# ethernet_poe.net
KiCad netlist of a schematic drawn in EAGLE
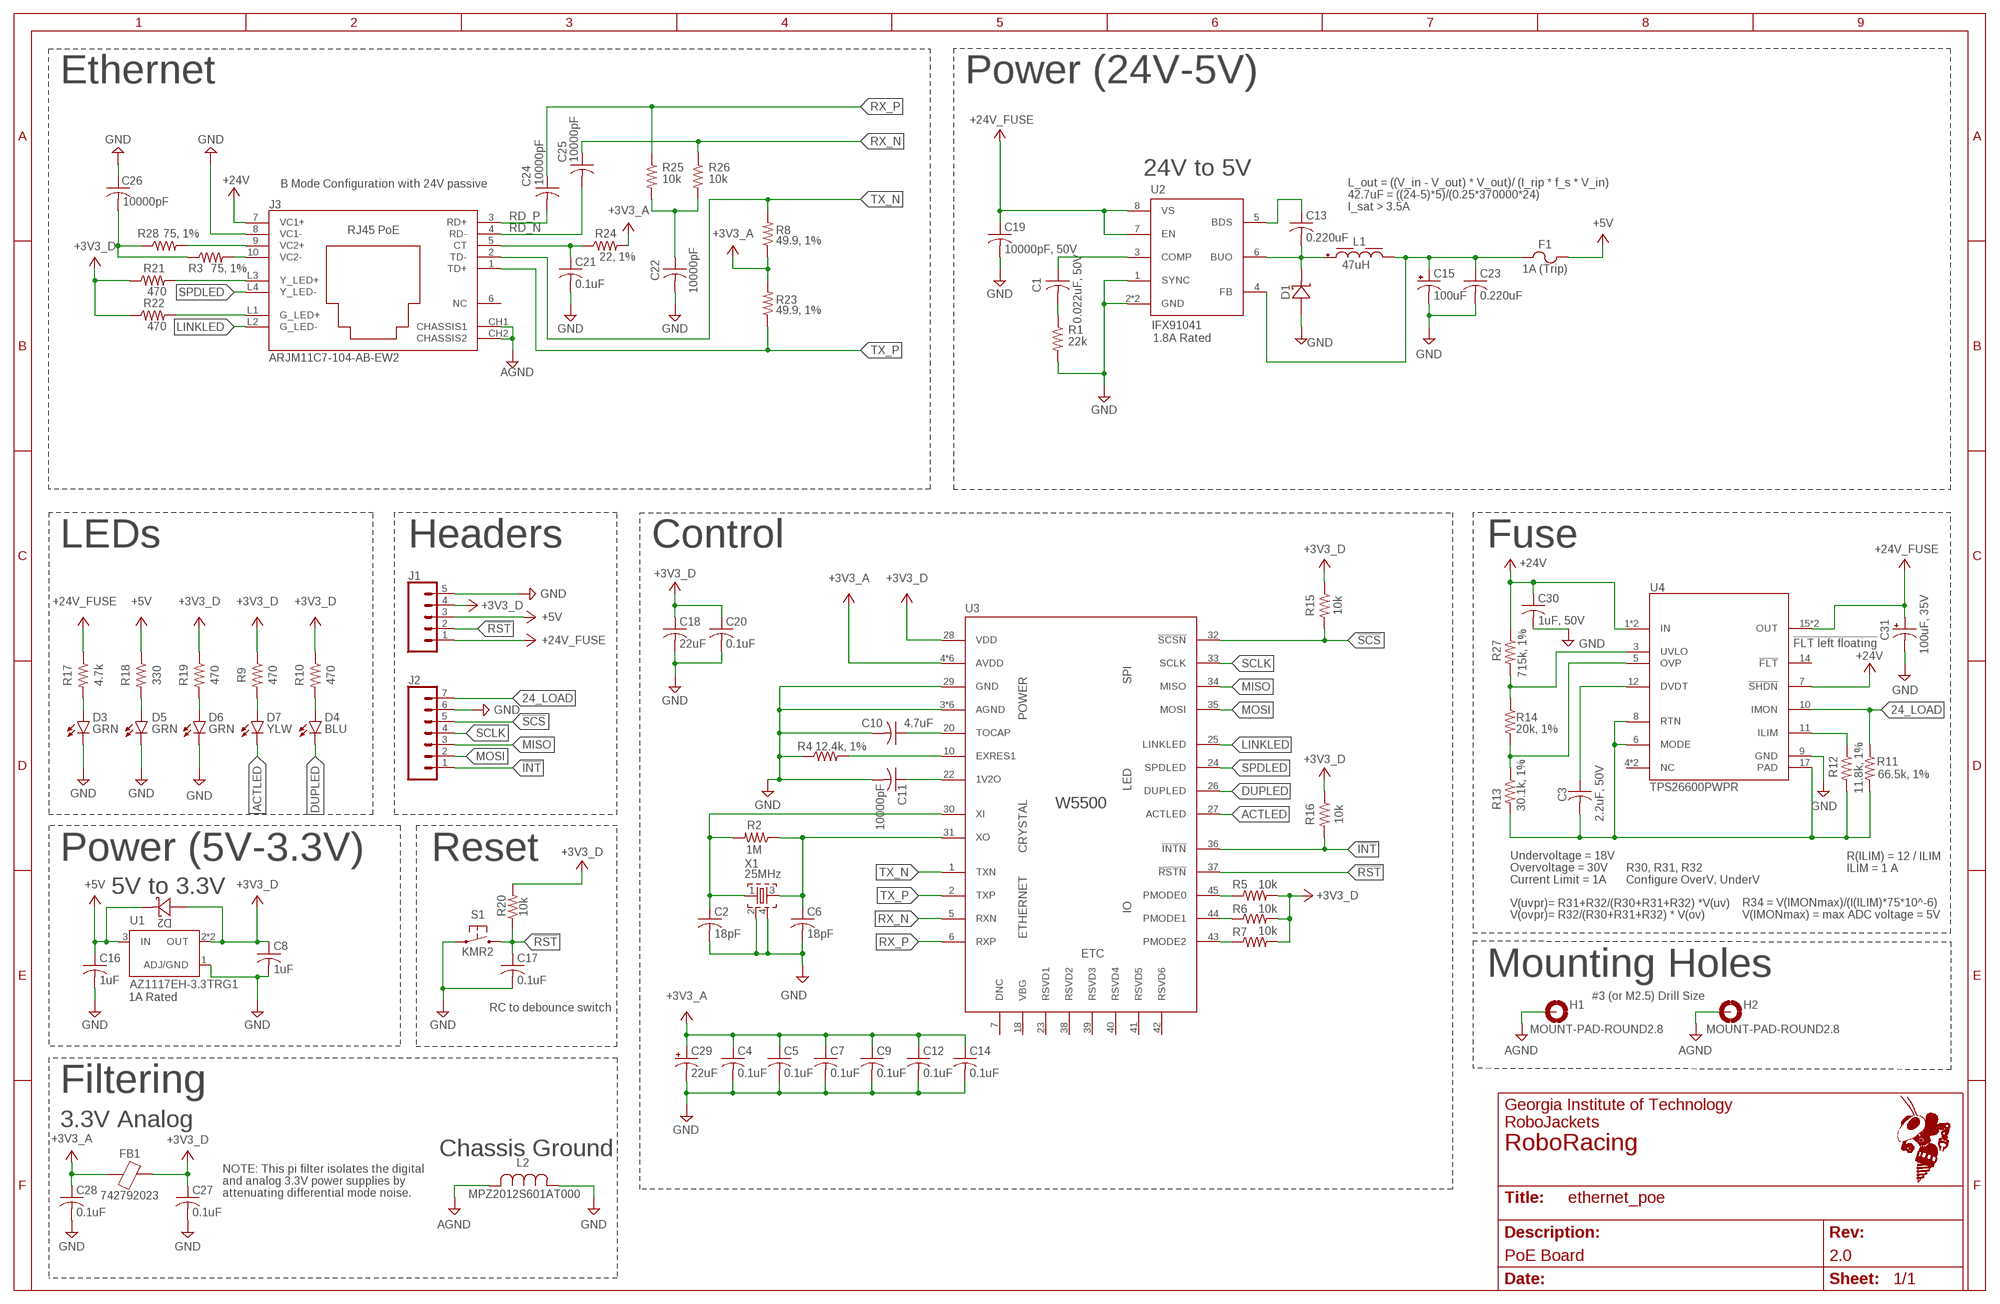
[diagram p0: schematic, sheet 1]

(export (version "E")
  (design (tool "Eeschema 10.0.6"))
  (components
    (comp (ref "C1")
      (value "0.022uF, 50V")
      (footprint "eagle-import:C0603")
      (libsource (lib "eagle-import") (part "rcl_334_C-USC0603"))
    )
    (comp (ref "C2")
      (value "18pF")
      (footprint "eagle-import:C0603")
      (libsource (lib "eagle-import") (part "rcl_334_C-USC0603"))
    )
    (comp (ref "C3")
      (value "2.2uF, 50V")
      (footprint "eagle-import:C0603")
      (libsource (lib "eagle-import") (part "rcl_334_C-USC0603"))
    )
    (comp (ref "C4")
      (value "0.1uF")
      (footprint "eagle-import:C0402")
      (libsource (lib "eagle-import") (part "C-USC0402"))
    )
    (comp (ref "C5")
      (value "0.1uF")
      (footprint "eagle-import:C0402")
      (libsource (lib "eagle-import") (part "C-USC0402"))
    )
    (comp (ref "C6")
      (value "18pF")
      (footprint "eagle-import:C0603")
      (libsource (lib "eagle-import") (part "rcl_334_C-USC0603"))
    )
    (comp (ref "C7")
      (value "0.1uF")
      (footprint "eagle-import:C0402")
      (libsource (lib "eagle-import") (part "C-USC0402"))
    )
    (comp (ref "C8")
      (value "1uF")
      (footprint "eagle-import:C0603")
      (libsource (lib "eagle-import") (part "rcl_334_C-USC0603"))
    )
    (comp (ref "C9")
      (value "0.1uF")
      (footprint "eagle-import:C0402")
      (libsource (lib "eagle-import") (part "C-USC0402"))
    )
    (comp (ref "C10")
      (value "4.7uF")
      (footprint "eagle-import:C0603")
      (libsource (lib "eagle-import") (part "rcl_334_C-USC0603"))
    )
    (comp (ref "C11")
      (value "10000pF")
      (footprint "eagle-import:C0402")
      (libsource (lib "eagle-import") (part "C-USC0402"))
    )
    (comp (ref "C12")
      (value "0.1uF")
      (footprint "eagle-import:C0402")
      (libsource (lib "eagle-import") (part "C-USC0402"))
    )
    (comp (ref "C13")
      (value "0.220uF")
      (footprint "eagle-import:C0603")
      (libsource (lib "eagle-import") (part "rcl_334_C-USC0603"))
    )
    (comp (ref "C14")
      (value "0.1uF")
      (footprint "eagle-import:C0402")
      (libsource (lib "eagle-import") (part "C-USC0402"))
    )
    (comp (ref "C15")
      (value "100uF")
      (footprint "eagle-import:E2-5")
      (libsource (lib "eagle-import") (part "CPOL-USE2-5"))
    )
    (comp (ref "C16")
      (value "1uF")
      (footprint "eagle-import:C0603")
      (libsource (lib "eagle-import") (part "rcl_334_C-USC0603"))
    )
    (comp (ref "C17")
      (value "0.1uF")
      (footprint "eagle-import:C0402")
      (libsource (lib "eagle-import") (part "C-USC0402"))
    )
    (comp (ref "C18")
      (value "22uF")
      (footprint "eagle-import:C0603")
      (libsource (lib "eagle-import") (part "rcl_334_C-USC0603"))
    )
    (comp (ref "C19")
      (value "10000pF, 50V")
      (footprint "eagle-import:C0603")
      (libsource (lib "eagle-import") (part "rcl_334_C-USC0603"))
    )
    (comp (ref "C20")
      (value "0.1uF")
      (footprint "eagle-import:C0402")
      (libsource (lib "eagle-import") (part "C-USC0402"))
    )
    (comp (ref "C21")
      (value "0.1uF")
      (footprint "eagle-import:C0402")
      (libsource (lib "eagle-import") (part "C-USC0402"))
    )
    (comp (ref "C22")
      (value "10000pF")
      (footprint "eagle-import:C0603")
      (libsource (lib "eagle-import") (part "rcl_334_C-USC0603"))
    )
    (comp (ref "C23")
      (value "0.220uF")
      (footprint "eagle-import:C0603")
      (libsource (lib "eagle-import") (part "rcl_334_C-USC0603"))
    )
    (comp (ref "C24")
      (value "10000pF")
      (footprint "eagle-import:C0402")
      (libsource (lib "eagle-import") (part "C-USC0402"))
    )
    (comp (ref "C25")
      (value "10000pF")
      (footprint "eagle-import:C0402")
      (libsource (lib "eagle-import") (part "C-USC0402"))
    )
    (comp (ref "C26")
      (value "10000pF")
      (footprint "eagle-import:C0603")
      (libsource (lib "eagle-import") (part "rcl_334_C-USC0603"))
    )
    (comp (ref "C27")
      (value "0.1uF")
      (footprint "eagle-import:C0603")
      (libsource (lib "eagle-import") (part "C-USC0603"))
    )
    (comp (ref "C28")
      (value "0.1uF")
      (footprint "eagle-import:C0603")
      (libsource (lib "eagle-import") (part "C-USC0603"))
    )
    (comp (ref "C29")
      (value "22uF")
      (footprint "eagle-import:PANASONIC_C")
      (libsource (lib "eagle-import") (part "22UF-POLAR-PANASONIC_C-35V-20%"))
    )
    (comp (ref "C30")
      (value "1uF, 50V")
      (footprint "eagle-import:C0603")
      (libsource (lib "eagle-import") (part "rcl_334_C-USC0603"))
    )
    (comp (ref "C31")
      (value "100uF, 35V")
      (footprint "eagle-import:E2,5-7")
      (libsource (lib "eagle-import") (part "CPOL-USE2.5-7"))
    )
    (comp (ref "D1")
      (value "NTS260ESFT3G")
      (footprint "eagle-import:SOD123FL_DIO")
      (libsource (lib "eagle-import") (part "NTS260ESFT3G"))
    )
    (comp (ref "D2")
      (value "NTS260ESFT3G")
      (footprint "eagle-import:SOD123FL_DIO")
      (libsource (lib "eagle-import") (part "NTS260ESFT3G"))
    )
    (comp (ref "D3")
      (value "GRN")
      (footprint "eagle-import:CHIP-LED0603")
      (libsource (lib "eagle-import") (part "LEDCHIP-LED0603"))
    )
    (comp (ref "D4")
      (value "BLU")
      (footprint "eagle-import:CHIP-LED0603")
      (libsource (lib "eagle-import") (part "LEDCHIP-LED0603"))
    )
    (comp (ref "D5")
      (value "GRN")
      (footprint "eagle-import:CHIP-LED0603")
      (libsource (lib "eagle-import") (part "LEDCHIP-LED0603"))
    )
    (comp (ref "D6")
      (value "GRN")
      (footprint "eagle-import:CHIP-LED0603")
      (libsource (lib "eagle-import") (part "LEDCHIP-LED0603"))
    )
    (comp (ref "D7")
      (value "YLW")
      (footprint "eagle-import:CHIP-LED0603")
      (libsource (lib "eagle-import") (part "LEDCHIP-LED0603"))
    )
    (comp (ref "F1")
      (value "1A (Trip)")
      (footprint "eagle-import:0ZCG_BEL")
      (libsource (lib "eagle-import") (part "0ZCG0050AF2C"))
    )
    (comp (ref "FB1")
      (value "742792023")
      (footprint "eagle-import:0805")
      (libsource (lib "eagle-import") (part "742792023"))
    )
    (comp (ref "H1")
      (value "MOUNT-PAD-ROUND2.8")
      (footprint "eagle-import:2,8-PAD")
      (libsource (lib "eagle-import") (part "MOUNT-PAD-ROUND2.8"))
    )
    (comp (ref "H2")
      (value "MOUNT-PAD-ROUND2.8")
      (footprint "eagle-import:2,8-PAD")
      (libsource (lib "eagle-import") (part "MOUNT-PAD-ROUND2.8"))
    )
    (comp (ref "J1")
      (value "CONN_05")
      (footprint "eagle-import:1X05")
      (libsource (lib "eagle-import") (part "CONN_05"))
    )
    (comp (ref "J2")
      (value "CONN_07")
      (footprint "eagle-import:1X07")
      (libsource (lib "eagle-import") (part "CONN_07"))
    )
    (comp (ref "J3")
      (value "ARJM11C7-104-AB-EW2")
      (footprint "eagle-import:CONN_EW_ABR")
      (libsource (lib "eagle-import") (part "ARJM11C7-104-AB-EW2"))
    )
    (comp (ref "L1")
      (value "47uH")
      (footprint "eagle-import:WE-PD_1210")
      (libsource (lib "eagle-import") (part "7447709470_7447709470"))
    )
    (comp (ref "L2")
      (value "MPZ2012S601AT000")
      (footprint "eagle-import:IND_2012_TDK")
      (libsource (lib "eagle-import") (part "MPZ2012S601AT000"))
    )
    (comp (ref "R1")
      (value "22k")
      (footprint "eagle-import:R0603")
      (libsource (lib "eagle-import") (part "rcl_334_R-US_R0603"))
    )
    (comp (ref "R2")
      (value "1M")
      (footprint "eagle-import:R0402")
      (libsource (lib "eagle-import") (part "R-US_R0402"))
    )
    (comp (ref "R3")
      (value "75, 1%")
      (footprint "eagle-import:R0603")
      (libsource (lib "eagle-import") (part "rcl_334_R-US_R0603"))
    )
    (comp (ref "R4")
      (value "12.4k, 1%")
      (footprint "eagle-import:R0603")
      (libsource (lib "eagle-import") (part "rcl_334_R-US_R0603"))
    )
    (comp (ref "R5")
      (value "10k")
      (footprint "eagle-import:R0603")
      (libsource (lib "eagle-import") (part "rcl_334_R-US_R0603"))
    )
    (comp (ref "R6")
      (value "10k")
      (footprint "eagle-import:R0603")
      (libsource (lib "eagle-import") (part "rcl_334_R-US_R0603"))
    )
    (comp (ref "R7")
      (value "10k")
      (footprint "eagle-import:R0603")
      (libsource (lib "eagle-import") (part "rcl_334_R-US_R0603"))
    )
    (comp (ref "R8")
      (value "49.9, 1%")
      (footprint "eagle-import:R0402")
      (libsource (lib "eagle-import") (part "R-US_R0402"))
    )
    (comp (ref "R9")
      (value "470")
      (footprint "eagle-import:R0603")
      (libsource (lib "eagle-import") (part "rcl_334_R-US_R0603"))
    )
    (comp (ref "R10")
      (value "470")
      (footprint "eagle-import:R0603")
      (libsource (lib "eagle-import") (part "rcl_334_R-US_R0603"))
    )
    (comp (ref "R11")
      (value "66.5k, 1%")
      (footprint "eagle-import:R0603")
      (libsource (lib "eagle-import") (part "rcl_334_R-US_R0603"))
    )
    (comp (ref "R12")
      (value "11.8k, 1%")
      (footprint "eagle-import:R0603")
      (libsource (lib "eagle-import") (part "rcl_334_R-US_R0603"))
    )
    (comp (ref "R13")
      (value "30.1k, 1%")
      (footprint "eagle-import:R0603")
      (libsource (lib "eagle-import") (part "rcl_334_R-US_R0603"))
    )
    (comp (ref "R14")
      (value "20k, 1%")
      (footprint "eagle-import:R0603")
      (libsource (lib "eagle-import") (part "rcl_334_R-US_R0603"))
    )
    (comp (ref "R15")
      (value "10k")
      (footprint "eagle-import:R0603")
      (libsource (lib "eagle-import") (part "rcl_334_R-US_R0603"))
    )
    (comp (ref "R16")
      (value "10k")
      (footprint "eagle-import:R0603")
      (libsource (lib "eagle-import") (part "rcl_334_R-US_R0603"))
    )
    (comp (ref "R17")
      (value "4.7k")
      (footprint "eagle-import:R0603")
      (libsource (lib "eagle-import") (part "rcl_334_R-US_R0603"))
    )
    (comp (ref "R18")
      (value "330")
      (footprint "eagle-import:R0603")
      (libsource (lib "eagle-import") (part "rcl_334_R-US_R0603"))
    )
    (comp (ref "R19")
      (value "470")
      (footprint "eagle-import:R0603")
      (libsource (lib "eagle-import") (part "rcl_334_R-US_R0603"))
    )
    (comp (ref "R20")
      (value "10k")
      (footprint "eagle-import:R0603")
      (libsource (lib "eagle-import") (part "rcl_334_R-US_R0603"))
    )
    (comp (ref "R21")
      (value "470")
      (footprint "eagle-import:R0603")
      (libsource (lib "eagle-import") (part "rcl_334_R-US_R0603"))
    )
    (comp (ref "R22")
      (value "470")
      (footprint "eagle-import:R0603")
      (libsource (lib "eagle-import") (part "rcl_334_R-US_R0603"))
    )
    (comp (ref "R23")
      (value "49.9, 1%")
      (footprint "eagle-import:R0402")
      (libsource (lib "eagle-import") (part "R-US_R0402"))
    )
    (comp (ref "R24")
      (value "22, 1%")
      (footprint "eagle-import:R0603")
      (libsource (lib "eagle-import") (part "rcl_334_R-US_R0603"))
    )
    (comp (ref "R25")
      (value "10k")
      (footprint "eagle-import:R0603")
      (libsource (lib "eagle-import") (part "rcl_334_R-US_R0603"))
    )
    (comp (ref "R26")
      (value "10k")
      (footprint "eagle-import:R0603")
      (libsource (lib "eagle-import") (part "rcl_334_R-US_R0603"))
    )
    (comp (ref "R27")
      (value "715k, 1%")
      (footprint "eagle-import:R0603")
      (libsource (lib "eagle-import") (part "rcl_334_R-US_R0603"))
    )
    (comp (ref "R28")
      (value "75, 1%")
      (footprint "eagle-import:R0603")
      (libsource (lib "eagle-import") (part "rcl_334_R-US_R0603"))
    )
    (comp (ref "S1")
      (value "KMR2")
      (footprint "eagle-import:KMR2")
      (libsource (lib "eagle-import") (part "KMR2"))
    )
    (comp (ref "U1")
      (value "AZ1117EH-3.3TRG1")
      (footprint "eagle-import:SOT230P700X180-4N")
      (libsource (lib "eagle-import") (part "AZ1117EH-3.3TRG1"))
    )
    (comp (ref "U2")
      (value "IFX91041")
      (footprint "eagle-import:SOIC-8-EXPOSED_PAD")
      (libsource (lib "eagle-import") (part "IFX91041"))
    )
    (comp (ref "U3")
      (value "W5500")
      (footprint "eagle-import:48-LQFP")
      (libsource (lib "eagle-import") (part "W5500"))
    )
    (comp (ref "U4")
      (value "TPS26600PWPR")
      (footprint "eagle-import:PWP0016H_N")
      (libsource (lib "eagle-import") (part "TPS26600PWPR"))
    )
    (comp (ref "X1")
      (value "25MHz")
      (footprint "eagle-import:OSCILLATOR-SMD-2.5X2")
      (libsource (lib "eagle-import") (part "ABM10W-25.0000MHZ-6-K1Z-T3"))
    )
  )
  (nets
    (net (code "1") (name "+3V3_A") (class "Default")
      (node (ref "C12") (pin "1") (pinfunction "1_1") (pintype "passive"))
      (node (ref "C14") (pin "1") (pinfunction "1_1") (pintype "passive"))
      (node (ref "C28") (pin "1") (pinfunction "1_1") (pintype "passive"))
      (node (ref "C29") (pin "+") (pinfunction "+_+") (pintype "passive"))
      (node (ref "C4") (pin "1") (pinfunction "1_1") (pintype "passive"))
      (node (ref "C5") (pin "1") (pinfunction "1_1") (pintype "passive"))
      (node (ref "C7") (pin "1") (pinfunction "1_1") (pintype "passive"))
      (node (ref "C9") (pin "1") (pinfunction "1_1") (pintype "passive"))
      (node (ref "FB1") (pin "1") (pinfunction "1_1") (pintype "passive"))
      (node (ref "R23") (pin "2") (pinfunction "2_2") (pintype "passive"))
      (node (ref "R24") (pin "2") (pinfunction "2_2") (pintype "passive"))
      (node (ref "R8") (pin "1") (pinfunction "1_1") (pintype "passive"))
      (node (ref "U3") (pin "11") (pinfunction "AVDD_11") (pintype "power_in"))
      (node (ref "U3") (pin "15") (pinfunction "AVDD_15") (pintype "power_in"))
      (node (ref "U3") (pin "17") (pinfunction "AVDD_17") (pintype "power_in"))
      (node (ref "U3") (pin "21") (pinfunction "AVDD_21") (pintype "power_in"))
      (node (ref "U3") (pin "4") (pinfunction "AVDD_4") (pintype "power_in"))
      (node (ref "U3") (pin "8") (pinfunction "AVDD_8") (pintype "power_in"))
    )
    (net (code "2") (name "+3V3_D") (class "Default")
      (node (ref "C18") (pin "1") (pinfunction "1_1") (pintype "passive"))
      (node (ref "C20") (pin "1") (pinfunction "1_1") (pintype "passive"))
      (node (ref "C27") (pin "1") (pinfunction "1_1") (pintype "passive"))
      (node (ref "C8") (pin "1") (pinfunction "1_1") (pintype "passive"))
      (node (ref "D2") (pin "2") (pinfunction "2_2") (pintype "passive"))
      (node (ref "FB1") (pin "2") (pinfunction "2_2") (pintype "passive"))
      (node (ref "J1") (pin "4") (pinfunction "4_4") (pintype "passive"))
      (node (ref "R10") (pin "1") (pinfunction "1_1") (pintype "passive"))
      (node (ref "R15") (pin "1") (pinfunction "1_1") (pintype "passive"))
      (node (ref "R16") (pin "1") (pinfunction "1_1") (pintype "passive"))
      (node (ref "R19") (pin "1") (pinfunction "1_1") (pintype "passive"))
      (node (ref "R20") (pin "2") (pinfunction "2_2") (pintype "passive"))
      (node (ref "R21") (pin "1") (pinfunction "1_1") (pintype "passive"))
      (node (ref "R22") (pin "1") (pinfunction "1_1") (pintype "passive"))
      (node (ref "R5") (pin "2") (pinfunction "2_2") (pintype "passive"))
      (node (ref "R6") (pin "2") (pinfunction "2_2") (pintype "passive"))
      (node (ref "R7") (pin "2") (pinfunction "2_2") (pintype "passive"))
      (node (ref "R9") (pin "1") (pinfunction "1_1") (pintype "passive"))
      (node (ref "U1") (pin "2") (pinfunction "OUT_2") (pintype "output"))
      (node (ref "U1") (pin "4") (pinfunction "OUT_4") (pintype "output"))
      (node (ref "U3") (pin "28") (pinfunction "VDD_28") (pintype "power_in"))
    )
    (net (code "3") (name "+5V") (class "Default")
      (node (ref "C16") (pin "1") (pinfunction "1_1") (pintype "passive"))
      (node (ref "D2") (pin "1") (pinfunction "1_1") (pintype "passive"))
      (node (ref "F1") (pin "2") (pinfunction "2_2") (pintype "passive"))
      (node (ref "J1") (pin "3") (pinfunction "3_3") (pintype "passive"))
      (node (ref "R18") (pin "1") (pinfunction "1_1") (pintype "passive"))
      (node (ref "U1") (pin "3") (pinfunction "IN_3") (pintype "input"))
    )
    (net (code "4") (name "+24V") (class "Default")
      (node (ref "C30") (pin "1") (pinfunction "1_1") (pintype "passive"))
      (node (ref "J3") (pin "7") (pinfunction "VC1+_7") (pintype "passive"))
      (node (ref "R27") (pin "1") (pinfunction "1_1") (pintype "passive"))
      (node (ref "U4") (pin "1") (pinfunction "IN_1") (pintype "power_in"))
      (node (ref "U4") (pin "2") (pinfunction "IN_2") (pintype "power_in"))
      (node (ref "U4") (pin "7") (pinfunction "~{SHDN}_7") (pintype "input"))
    )
    (net (code "5") (name "+24V_FUSE") (class "Default")
      (node (ref "C19") (pin "1") (pinfunction "1_1") (pintype "passive"))
      (node (ref "C31") (pin "+") (pinfunction "+_+") (pintype "passive"))
      (node (ref "J1") (pin "1") (pinfunction "1_1") (pintype "passive"))
      (node (ref "R17") (pin "1") (pinfunction "1_1") (pintype "passive"))
      (node (ref "U2") (pin "7") (pinfunction "EN_7") (pintype "input"))
      (node (ref "U2") (pin "8") (pinfunction "VS_8") (pintype "power_in"))
      (node (ref "U4") (pin "15") (pinfunction "OUT_15") (pintype "power_in"))
      (node (ref "U4") (pin "16") (pinfunction "OUT_16") (pintype "power_in"))
    )
    (net (code "6") (name "/RD_N") (class "Default")
      (node (ref "C25") (pin "2") (pinfunction "2_2") (pintype "passive"))
      (node (ref "J3") (pin "4") (pinfunction "RD-_4") (pintype "passive"))
    )
    (net (code "7") (name "/RD_P") (class "Default")
      (node (ref "C24") (pin "2") (pinfunction "2_2") (pintype "passive"))
      (node (ref "J3") (pin "3") (pinfunction "RD+_3") (pintype "passive"))
    )
    (net (code "8") (name "/~{INT}") (class "Default")
      (node (ref "J2") (pin "1") (pinfunction "1_1") (pintype "passive"))
      (node (ref "R16") (pin "2") (pinfunction "2_2") (pintype "passive"))
      (node (ref "U3") (pin "36") (pinfunction "~{INTN}_36") (pintype "output"))
    )
    (net (code "9") (name "/~{RST}") (class "Default")
      (node (ref "C17") (pin "1") (pinfunction "1_1") (pintype "passive"))
      (node (ref "J1") (pin "2") (pinfunction "2_2") (pintype "passive"))
      (node (ref "R20") (pin "1") (pinfunction "1_1") (pintype "passive"))
      (node (ref "S1") (pin "2.1") (pinfunction "2_2.1") (pintype "passive"))
      (node (ref "S1") (pin "2.2") (pinfunction "2_2.2") (pintype "passive"))
      (node (ref "U3") (pin "37") (pinfunction "~{RSTN}_37") (pintype "input"))
    )
    (net (code "10") (name "/~{SCS}") (class "Default")
      (node (ref "J2") (pin "5") (pinfunction "5_5") (pintype "passive"))
      (node (ref "R15") (pin "2") (pinfunction "2_2") (pintype "passive"))
      (node (ref "U3") (pin "32") (pinfunction "~{SCSN}_32") (pintype "input"))
    )
    (net (code "11") (name "24_LOAD") (class "Default")
      (node (ref "J2") (pin "7") (pinfunction "7_7") (pintype "passive"))
      (node (ref "R11") (pin "1") (pinfunction "1_1") (pintype "passive"))
      (node (ref "U4") (pin "10") (pinfunction "IMON_10") (pintype "output"))
    )
    (net (code "12") (name "ACTLED") (class "Default")
      (node (ref "D7") (pin "C") (pinfunction "C_C") (pintype "passive"))
      (node (ref "U3") (pin "27") (pinfunction "ACTLED_27") (pintype "output"))
    )
    (net (code "13") (name "AGND") (class "Default")
      (node (ref "H1") (pin "B2,8") (pinfunction "MOUNT_B2,8") (pintype "passive"))
      (node (ref "H2") (pin "B2,8") (pinfunction "MOUNT_B2,8") (pintype "passive"))
      (node (ref "J3") (pin "CH1") (pinfunction "CHASSIS1_CH1") (pintype "passive"))
      (node (ref "J3") (pin "CH2") (pinfunction "CHASSIS2_CH2") (pintype "passive"))
      (node (ref "L2") (pin "2") (pinfunction "2_2") (pintype "passive"))
    )
    (net (code "14") (name "DUPLED") (class "Default")
      (node (ref "D4") (pin "C") (pinfunction "C_C") (pintype "passive"))
      (node (ref "U3") (pin "26") (pinfunction "DUPLED_26") (pintype "output"))
    )
    (net (code "15") (name "GND") (class "Default")
      (node (ref "C10") (pin "2") (pinfunction "2_2") (pintype "passive"))
      (node (ref "C11") (pin "2") (pinfunction "2_2") (pintype "passive"))
      (node (ref "C12") (pin "2") (pinfunction "2_2") (pintype "passive"))
      (node (ref "C14") (pin "2") (pinfunction "2_2") (pintype "passive"))
      (node (ref "C15") (pin "-") (pinfunction "-_-") (pintype "passive"))
      (node (ref "C16") (pin "2") (pinfunction "2_2") (pintype "passive"))
      (node (ref "C17") (pin "2") (pinfunction "2_2") (pintype "passive"))
      (node (ref "C18") (pin "2") (pinfunction "2_2") (pintype "passive"))
      (node (ref "C19") (pin "2") (pinfunction "2_2") (pintype "passive"))
      (node (ref "C2") (pin "2") (pinfunction "2_2") (pintype "passive"))
      (node (ref "C20") (pin "2") (pinfunction "2_2") (pintype "passive"))
      (node (ref "C21") (pin "2") (pinfunction "2_2") (pintype "passive"))
      (node (ref "C22") (pin "2") (pinfunction "2_2") (pintype "passive"))
      (node (ref "C23") (pin "2") (pinfunction "2_2") (pintype "passive"))
      (node (ref "C26") (pin "1") (pinfunction "1_1") (pintype "passive"))
      (node (ref "C27") (pin "2") (pinfunction "2_2") (pintype "passive"))
      (node (ref "C28") (pin "2") (pinfunction "2_2") (pintype "passive"))
      (node (ref "C29") (pin "-") (pinfunction "-_-") (pintype "passive"))
      (node (ref "C30") (pin "2") (pinfunction "2_2") (pintype "passive"))
      (node (ref "C31") (pin "-") (pinfunction "-_-") (pintype "passive"))
      (node (ref "C4") (pin "2") (pinfunction "2_2") (pintype "passive"))
      (node (ref "C5") (pin "2") (pinfunction "2_2") (pintype "passive"))
      (node (ref "C6") (pin "2") (pinfunction "2_2") (pintype "passive"))
      (node (ref "C7") (pin "2") (pinfunction "2_2") (pintype "passive"))
      (node (ref "C8") (pin "2") (pinfunction "2_2") (pintype "passive"))
      (node (ref "C9") (pin "2") (pinfunction "2_2") (pintype "passive"))
      (node (ref "D1") (pin "2") (pinfunction "2_2") (pintype "passive"))
      (node (ref "D3") (pin "C") (pinfunction "C_C") (pintype "passive"))
      (node (ref "D5") (pin "C") (pinfunction "C_C") (pintype "passive"))
      (node (ref "D6") (pin "C") (pinfunction "C_C") (pintype "passive"))
      (node (ref "J1") (pin "5") (pinfunction "5_5") (pintype "passive"))
      (node (ref "J2") (pin "6") (pinfunction "6_6") (pintype "passive"))
      (node (ref "J3") (pin "8") (pinfunction "VC1-_8") (pintype "passive"))
      (node (ref "L2") (pin "1") (pinfunction "1_1") (pintype "passive"))
      (node (ref "R1") (pin "2") (pinfunction "2_2") (pintype "passive"))
      (node (ref "R4") (pin "1") (pinfunction "1_1") (pintype "passive"))
      (node (ref "S1") (pin "1.1") (pinfunction "1_1.1") (pintype "passive"))
      (node (ref "S1") (pin "1.2") (pinfunction "1_1.2") (pintype "passive"))
      (node (ref "U1") (pin "1") (pinfunction "ADJ/GND_1") (pintype "power_in"))
      (node (ref "U2") (pin "1") (pinfunction "SYNC_1") (pintype "input"))
      (node (ref "U2") (pin "2") (pinfunction "GND_2") (pintype "power_in"))
      (node (ref "U2") (pin "9") (pinfunction "GND_9") (pintype "power_in"))
      (node (ref "U3") (pin "14") (pinfunction "AGND_14") (pintype "power_in"))
      (node (ref "U3") (pin "16") (pinfunction "AGND_16") (pintype "power_in"))
      (node (ref "U3") (pin "19") (pinfunction "AGND_19") (pintype "power_in"))
      (node (ref "U3") (pin "29") (pinfunction "GND_29") (pintype "power_in"))
      (node (ref "U3") (pin "3") (pinfunction "AGND_3") (pintype "power_in"))
      (node (ref "U3") (pin "48") (pinfunction "AGND_48") (pintype "power_in"))
      (node (ref "U3") (pin "9") (pinfunction "AGND_9") (pintype "power_in"))
      (node (ref "U4") (pin "9") (pinfunction "GND_9") (pintype "power_in"))
      (node (ref "X1") (pin "2") (pinfunction "SHD1_2") (pintype "passive"))
      (node (ref "X1") (pin "4") (pinfunction "SHD2_4") (pintype "passive"))
    )
    (net (code "16") (name "LINKLED") (class "Default")
      (node (ref "J3") (pin "L2") (pinfunction "G_LED-_L2") (pintype "passive"))
      (node (ref "U3") (pin "25") (pinfunction "LINKLED_25") (pintype "output"))
    )
    (net (code "17") (name "MISO") (class "Default")
      (node (ref "J2") (pin "3") (pinfunction "3_3") (pintype "passive"))
      (node (ref "U3") (pin "34") (pinfunction "MISO_34") (pintype "output"))
    )
    (net (code "18") (name "MOSI") (class "Default")
      (node (ref "J2") (pin "2") (pinfunction "2_2") (pintype "passive"))
      (node (ref "U3") (pin "35") (pinfunction "MOSI_35") (pintype "input"))
    )
    (net (code "19") (name "Net-(C1-Pad2)") (class "Default")
      (node (ref "C1") (pin "2") (pinfunction "2_2") (pintype "passive"))
      (node (ref "R1") (pin "1") (pinfunction "1_1") (pintype "passive"))
    )
    (net (code "20") (name "Net-(C22-Pad1)") (class "Default")
      (node (ref "C22") (pin "1") (pinfunction "1_1") (pintype "passive"))
      (node (ref "R25") (pin "2") (pinfunction "2_2") (pintype "passive"))
      (node (ref "R26") (pin "2") (pinfunction "2_2") (pintype "passive"))
    )
    (net (code "21") (name "Net-(C26-Pad2)") (class "Default")
      (node (ref "C26") (pin "2") (pinfunction "2_2") (pintype "passive"))
      (node (ref "R28") (pin "1") (pinfunction "1_1") (pintype "passive"))
      (node (ref "R3") (pin "1") (pinfunction "1_1") (pintype "passive"))
    )
    (net (code "22") (name "Net-(D3-PadA)") (class "Default")
      (node (ref "D3") (pin "A") (pinfunction "A_A") (pintype "passive"))
      (node (ref "R17") (pin "2") (pinfunction "2_2") (pintype "passive"))
    )
    (net (code "23") (name "Net-(D4-PadA)") (class "Default")
      (node (ref "D4") (pin "A") (pinfunction "A_A") (pintype "passive"))
      (node (ref "R10") (pin "2") (pinfunction "2_2") (pintype "passive"))
    )
    (net (code "24") (name "Net-(D5-PadA)") (class "Default")
      (node (ref "D5") (pin "A") (pinfunction "A_A") (pintype "passive"))
      (node (ref "R18") (pin "2") (pinfunction "2_2") (pintype "passive"))
    )
    (net (code "25") (name "Net-(D6-PadA)") (class "Default")
      (node (ref "D6") (pin "A") (pinfunction "A_A") (pintype "passive"))
      (node (ref "R19") (pin "2") (pinfunction "2_2") (pintype "passive"))
    )
    (net (code "26") (name "Net-(D7-PadA)") (class "Default")
      (node (ref "D7") (pin "A") (pinfunction "A_A") (pintype "passive"))
      (node (ref "R9") (pin "2") (pinfunction "2_2") (pintype "passive"))
    )
    (net (code "27") (name "Net-(J3-CT)") (class "Default")
      (node (ref "C21") (pin "1") (pinfunction "1_1") (pintype "passive"))
      (node (ref "J3") (pin "5") (pinfunction "CT_5") (pintype "passive"))
      (node (ref "R24") (pin "1") (pinfunction "1_1") (pintype "passive"))
    )
    (net (code "28") (name "Net-(J3-G_LED+)") (class "Default")
      (node (ref "J3") (pin "L1") (pinfunction "G_LED+_L1") (pintype "passive"))
      (node (ref "R22") (pin "2") (pinfunction "2_2") (pintype "passive"))
    )
    (net (code "29") (name "Net-(J3-VC2+)") (class "Default")
      (node (ref "J3") (pin "9") (pinfunction "VC2+_9") (pintype "passive"))
      (node (ref "R28") (pin "2") (pinfunction "2_2") (pintype "passive"))
    )
    (net (code "30") (name "Net-(J3-VC2-)") (class "Default")
      (node (ref "J3") (pin "10") (pinfunction "VC2-_10") (pintype "passive"))
      (node (ref "R3") (pin "2") (pinfunction "2_2") (pintype "passive"))
    )
    (net (code "31") (name "Net-(J3-Y_LED+)") (class "Default")
      (node (ref "J3") (pin "L3") (pinfunction "Y_LED+_L3") (pintype "passive"))
      (node (ref "R21") (pin "2") (pinfunction "2_2") (pintype "passive"))
    )
    (net (code "32") (name "Net-(U2-BDS)") (class "Default")
      (node (ref "C13") (pin "1") (pinfunction "1_1") (pintype "passive"))
      (node (ref "U2") (pin "5") (pinfunction "BDS_5") (pintype "bidirectional"))
    )
    (net (code "33") (name "Net-(U2-BUO)") (class "Default")
      (node (ref "C13") (pin "2") (pinfunction "2_2") (pintype "passive"))
      (node (ref "D1") (pin "1") (pinfunction "1_1") (pintype "passive"))
      (node (ref "L1") (pin "1") (pinfunction "1_1") (pintype "passive"))
      (node (ref "U2") (pin "6") (pinfunction "BUO_6") (pintype "bidirectional"))
    )
    (net (code "34") (name "Net-(U2-COMP)") (class "Default")
      (node (ref "C1") (pin "1") (pinfunction "1_1") (pintype "passive"))
      (node (ref "U2") (pin "3") (pinfunction "COMP_3") (pintype "bidirectional"))
    )
    (net (code "35") (name "Net-(U2-FB)") (class "Default")
      (node (ref "C15") (pin "+") (pinfunction "+_+") (pintype "passive"))
      (node (ref "C23") (pin "1") (pinfunction "1_1") (pintype "passive"))
      (node (ref "F1") (pin "1") (pinfunction "1_1") (pintype "passive"))
      (node (ref "L1") (pin "2") (pinfunction "2_2") (pintype "passive"))
      (node (ref "U2") (pin "4") (pinfunction "FB_4") (pintype "bidirectional"))
    )
    (net (code "36") (name "Net-(U3-1V2O)") (class "Default")
      (node (ref "C11") (pin "1") (pinfunction "1_1") (pintype "passive"))
      (node (ref "U3") (pin "22") (pinfunction "1V2O_22") (pintype "output"))
    )
    (net (code "37") (name "Net-(U3-EXRES1)") (class "Default")
      (node (ref "R4") (pin "2") (pinfunction "2_2") (pintype "passive"))
      (node (ref "U3") (pin "10") (pinfunction "EXRES1_10") (pintype "output"))
    )
    (net (code "38") (name "Net-(U3-PMODE0)") (class "Default")
      (node (ref "R5") (pin "1") (pinfunction "1_1") (pintype "passive"))
      (node (ref "U3") (pin "45") (pinfunction "PMODE0_45") (pintype "input"))
    )
    (net (code "39") (name "Net-(U3-PMODE1)") (class "Default")
      (node (ref "R6") (pin "1") (pinfunction "1_1") (pintype "passive"))
      (node (ref "U3") (pin "44") (pinfunction "PMODE1_44") (pintype "input"))
    )
    (net (code "40") (name "Net-(U3-PMODE2)") (class "Default")
      (node (ref "R7") (pin "1") (pinfunction "1_1") (pintype "passive"))
      (node (ref "U3") (pin "43") (pinfunction "PMODE2_43") (pintype "input"))
    )
    (net (code "41") (name "Net-(U3-TOCAP)") (class "Default")
      (node (ref "C10") (pin "1") (pinfunction "1_1") (pintype "passive"))
      (node (ref "U3") (pin "20") (pinfunction "TOCAP_20") (pintype "output"))
    )
    (net (code "42") (name "Net-(U3-XI)") (class "Default")
      (node (ref "C2") (pin "1") (pinfunction "1_1") (pintype "passive"))
      (node (ref "R2") (pin "2") (pinfunction "2_2") (pintype "passive"))
      (node (ref "U3") (pin "30") (pinfunction "XI_30") (pintype "bidirectional"))
      (node (ref "X1") (pin "1") (pinfunction "IN_1") (pintype "passive"))
    )
    (net (code "43") (name "Net-(U3-XO)") (class "Default")
      (node (ref "C6") (pin "1") (pinfunction "1_1") (pintype "passive"))
      (node (ref "R2") (pin "1") (pinfunction "1_1") (pintype "passive"))
      (node (ref "U3") (pin "31") (pinfunction "XO_31") (pintype "bidirectional"))
      (node (ref "X1") (pin "3") (pinfunction "OUT_3") (pintype "passive"))
    )
    (net (code "44") (name "Net-(U4-DVDT)") (class "Default")
      (node (ref "C3") (pin "1") (pinfunction "1_1") (pintype "passive"))
      (node (ref "U4") (pin "12") (pinfunction "DVDT_12") (pintype "input"))
    )
    (net (code "45") (name "Net-(U4-ILIM)") (class "Default")
      (node (ref "R12") (pin "1") (pinfunction "1_1") (pintype "passive"))
      (node (ref "U4") (pin "11") (pinfunction "ILIM_11") (pintype "output"))
    )
    (net (code "46") (name "Net-(U4-MODE)") (class "Default")
      (node (ref "C3") (pin "2") (pinfunction "2_2") (pintype "passive"))
      (node (ref "R11") (pin "2") (pinfunction "2_2") (pintype "passive"))
      (node (ref "R12") (pin "2") (pinfunction "2_2") (pintype "passive"))
      (node (ref "R13") (pin "2") (pinfunction "2_2") (pintype "passive"))
      (node (ref "U4") (pin "17") (pinfunction "PAD_17") (pintype "power_in"))
      (node (ref "U4") (pin "6") (pinfunction "MODE_6") (pintype "input"))
      (node (ref "U4") (pin "8") (pinfunction "RTN_8") (pintype "input"))
    )
    (net (code "47") (name "Net-(U4-OVP)") (class "Default")
      (node (ref "R13") (pin "1") (pinfunction "1_1") (pintype "passive"))
      (node (ref "R14") (pin "2") (pinfunction "2_2") (pintype "passive"))
      (node (ref "U4") (pin "5") (pinfunction "OVP_5") (pintype "input"))
    )
    (net (code "48") (name "Net-(U4-UVLO)") (class "Default")
      (node (ref "R14") (pin "1") (pinfunction "1_1") (pintype "passive"))
      (node (ref "R27") (pin "2") (pinfunction "2_2") (pintype "passive"))
      (node (ref "U4") (pin "3") (pinfunction "UVLO_3") (pintype "input"))
    )
    (net (code "49") (name "RX_N") (class "Default")
      (node (ref "C25") (pin "1") (pinfunction "1_1") (pintype "passive"))
      (node (ref "R26") (pin "1") (pinfunction "1_1") (pintype "passive"))
      (node (ref "U3") (pin "5") (pinfunction "RXN_5") (pintype "input"))
    )
    (net (code "50") (name "RX_P") (class "Default")
      (node (ref "C24") (pin "1") (pinfunction "1_1") (pintype "passive"))
      (node (ref "R25") (pin "1") (pinfunction "1_1") (pintype "passive"))
      (node (ref "U3") (pin "6") (pinfunction "RXP_6") (pintype "input"))
    )
    (net (code "51") (name "SCLK") (class "Default")
      (node (ref "J2") (pin "4") (pinfunction "4_4") (pintype "passive"))
      (node (ref "U3") (pin "33") (pinfunction "SCLK_33") (pintype "input"))
    )
    (net (code "52") (name "SPDLED") (class "Default")
      (node (ref "J3") (pin "L4") (pinfunction "Y_LED-_L4") (pintype "passive"))
      (node (ref "U3") (pin "24") (pinfunction "SPDLED_24") (pintype "output"))
    )
    (net (code "53") (name "TX_N") (class "Default")
      (node (ref "J3") (pin "2") (pinfunction "TD-_2") (pintype "passive"))
      (node (ref "R8") (pin "2") (pinfunction "2_2") (pintype "passive"))
      (node (ref "U3") (pin "1") (pinfunction "TXN_1") (pintype "output"))
    )
    (net (code "54") (name "TX_P") (class "Default")
      (node (ref "J3") (pin "1") (pinfunction "TD+_1") (pintype "passive"))
      (node (ref "R23") (pin "1") (pinfunction "1_1") (pintype "passive"))
      (node (ref "U3") (pin "2") (pinfunction "TXP_2") (pintype "output"))
    )
    (net (code "55") (name "unconnected-(J3-NC-Pad6)") (class "Default")
      (node (ref "J3") (pin "6") (pinfunction "NC_6") (pintype "no_connect"))
    )
    (net (code "56") (name "unconnected-(U3-DNC-Pad7)") (class "Default")
      (node (ref "U3") (pin "7") (pinfunction "DNC_7") (pintype "no_connect"))
    )
    (net (code "57") (name "unconnected-(U3-RSVD1-Pad23)") (class "Default")
      (node (ref "U3") (pin "23") (pinfunction "RSVD1_23") (pintype "input"))
    )
    (net (code "58") (name "unconnected-(U3-RSVD2-Pad38)") (class "Default")
      (node (ref "U3") (pin "38") (pinfunction "RSVD2_38") (pintype "input"))
    )
    (net (code "59") (name "unconnected-(U3-RSVD3-Pad39)") (class "Default")
      (node (ref "U3") (pin "39") (pinfunction "RSVD3_39") (pintype "input"))
    )
    (net (code "60") (name "unconnected-(U3-RSVD4-Pad40)") (class "Default")
      (node (ref "U3") (pin "40") (pinfunction "RSVD4_40") (pintype "input"))
    )
    (net (code "61") (name "unconnected-(U3-RSVD5-Pad41)") (class "Default")
      (node (ref "U3") (pin "41") (pinfunction "RSVD5_41") (pintype "input"))
    )
    (net (code "62") (name "unconnected-(U3-RSVD6-Pad42)") (class "Default")
      (node (ref "U3") (pin "42") (pinfunction "RSVD6_42") (pintype "input"))
    )
    (net (code "63") (name "unconnected-(U3-VBG-Pad18)") (class "Default")
      (node (ref "U3") (pin "18") (pinfunction "VBG_18") (pintype "no_connect"))
    )
    (net (code "64") (name "unconnected-(U4-NC-Pad4)") (class "Default")
      (node (ref "U4") (pin "4") (pinfunction "NC_4") (pintype "no_connect"))
    )
    (net (code "65") (name "unconnected-(U4-NC-Pad13)") (class "Default")
      (node (ref "U4") (pin "13") (pinfunction "NC_13") (pintype "no_connect"))
    )
    (net (code "66") (name "unconnected-(U4-~{FLT}-Pad14)") (class "Default")
      (node (ref "U4") (pin "14") (pinfunction "~{FLT}_14") (pintype "open_collector"))
    )
  )
)
